# rpi_pwrspl.net
KiCad netlist of a schematic drawn in EAGLE
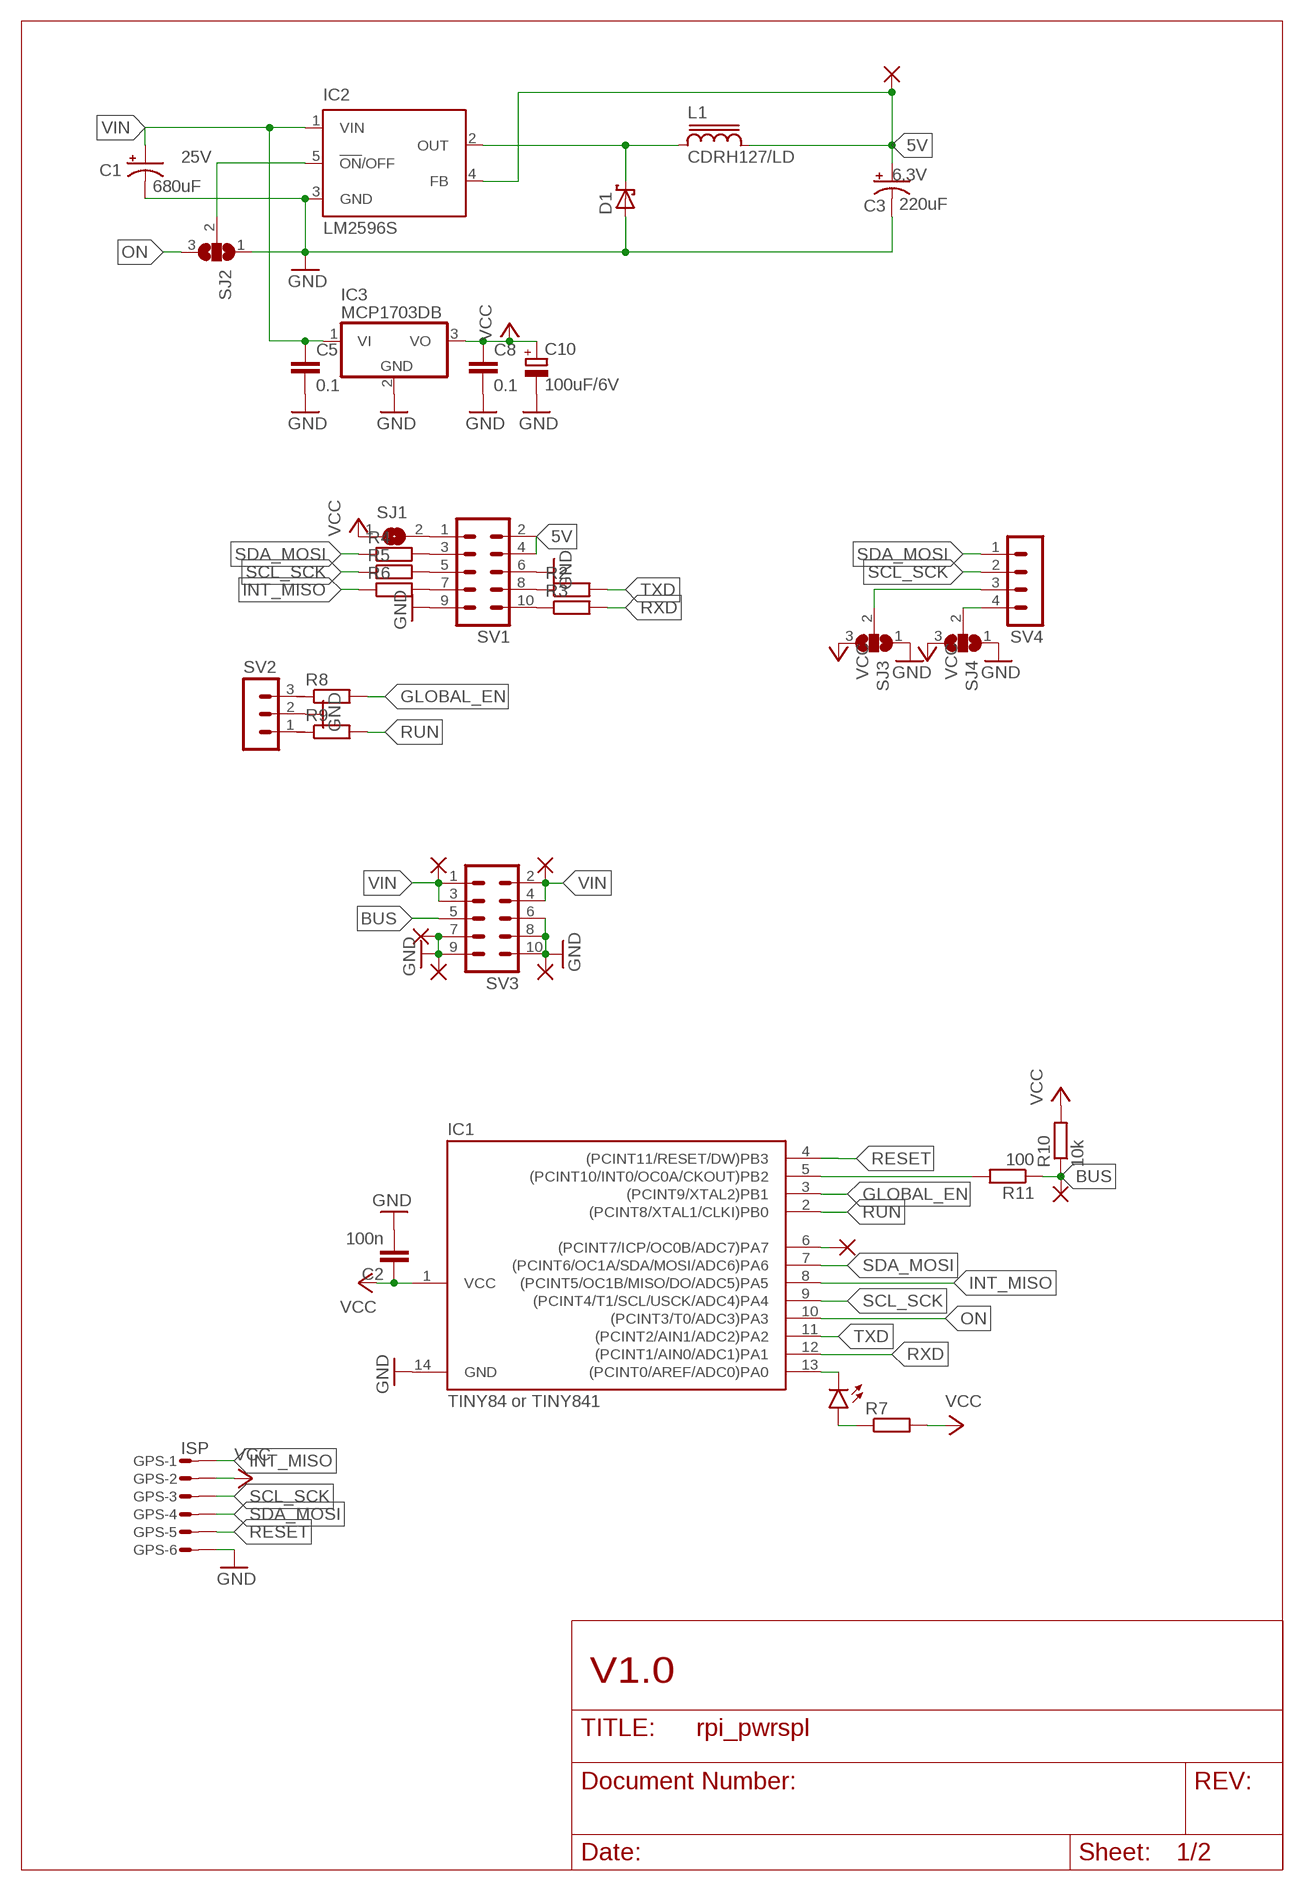
[diagram p0: schematic, sheet 1]

(export (version "E")
  (design (tool "Eeschema 10.0.6"))
  (components
    (comp (ref "C1")
      (value "680uF")
      (footprint "eagle-import:E5-10,5")
      (fields (field (name "VOLTAGE") "25V"))
      (libsource (lib "eagle-import") (part "CPOL-USE5-10.5"))
    )
    (comp (ref "C2")
      (value "100n")
      (footprint "eagle-import:C0805")
      (libsource (lib "eagle-import") (part "C-EUC0805"))
    )
    (comp (ref "C3")
      (value "220uF")
      (footprint "eagle-import:UD-6,3X5,8_NICHICON")
      (fields (field (name "VOLTAGE") "6.3V"))
      (libsource (lib "eagle-import") (part "CPOL-USUD-6,3X5,8"))
    )
    (comp (ref "C5")
      (value "0.1")
      (footprint "eagle-import:C0805")
      (libsource (lib "eagle-import") (part "C-EUC0805"))
    )
    (comp (ref "C8")
      (value "0.1")
      (footprint "eagle-import:C0805")
      (libsource (lib "eagle-import") (part "C-EUC0805"))
    )
    (comp (ref "C10")
      (value "100uF/6V")
      (footprint "eagle-import:B_3528-21R")
      (libsource (lib "eagle-import") (part "CPOL-EUB/3528-21R"))
    )
    (comp (ref "D1")
      (value "SCHOTTKY-DIODESMD")
      (footprint "eagle-import:SMB")
      (libsource (lib "eagle-import") (part "SCHOTTKY-DIODESMD"))
    )
    (comp (ref "GPS")
      (value "ISP")
      (footprint "eagle-import:MICROMATCH-6SMD")
      (libsource (lib "eagle-import") (part "MICROMATCH-6SMD"))
    )
    (comp (ref "IC1")
      (value "TINY84 or TINY841")
      (footprint "eagle-import:SOIC14")
      (libsource (lib "eagle-import") (part "TINY24/44/84-SSU"))
    )
    (comp (ref "IC2")
      (value "LM2596S")
      (footprint "eagle-import:TO263-5")
      (fields (field (name "MF") "NATIONAL SEMICONDUCTOR") (field (name "MPN") "LM2596S-ADJ/NOPB"))
      (libsource (lib "eagle-import") (part "LM2596S"))
    )
    (comp (ref "IC3")
      (value "MCP1703DB")
      (footprint "eagle-import:SOT223")
      (libsource (lib "eagle-import") (part "MCP1703DB"))
    )
    (comp (ref "L1")
      (value "CDRH127/LD")
      (footprint "eagle-import:CDRH127_LD")
      (libsource (lib "eagle-import") (part "CDRH127/LD"))
    )
    (comp (ref "LED")
      (value "LEDCHIPLED_0805")
      (footprint "eagle-import:CHIPLED_0805")
      (libsource (lib "eagle-import") (part "LEDCHIPLED_0805"))
    )
    (comp (ref "PAD1")
      (value "1,6/0,9")
      (footprint "eagle-import:1,6_0,9")
      (libsource (lib "eagle-import") (part "1,6/0,9"))
    )
    (comp (ref "PAD2")
      (value "1,6/0,9")
      (footprint "eagle-import:1,6_0,9")
      (libsource (lib "eagle-import") (part "1,6/0,9"))
    )
    (comp (ref "PAD3")
      (value "1,6/0,9")
      (footprint "eagle-import:1,6_0,9")
      (libsource (lib "eagle-import") (part "1,6/0,9"))
    )
    (comp (ref "PAD4")
      (value "2,54/1,1")
      (footprint "eagle-import:2,54_1,1")
      (libsource (lib "eagle-import") (part "2,54/1,1"))
    )
    (comp (ref "PAD5")
      (value "2,54/1,1")
      (footprint "eagle-import:2,54_1,1")
      (libsource (lib "eagle-import") (part "2,54/1,1"))
    )
    (comp (ref "PAD6")
      (value "1,6/0,9")
      (footprint "eagle-import:1,6_0,9")
      (libsource (lib "eagle-import") (part "1,6/0,9"))
    )
    (comp (ref "PAD7")
      (value "1,6/0,9")
      (footprint "eagle-import:1,6_0,9")
      (libsource (lib "eagle-import") (part "1,6/0,9"))
    )
    (comp (ref "PAD8")
      (value "2,54/1,1")
      (footprint "eagle-import:2,54_1,1")
      (libsource (lib "eagle-import") (part "2,54/1,1"))
    )
    (comp (ref "R2")
      (value "R-EU_M0805")
      (footprint "eagle-import:M0805")
      (libsource (lib "eagle-import") (part "R-EU_M0805"))
    )
    (comp (ref "R3")
      (value "R-EU_M0805")
      (footprint "eagle-import:M0805")
      (libsource (lib "eagle-import") (part "R-EU_M0805"))
    )
    (comp (ref "R4")
      (value "R-EU_M0805")
      (footprint "eagle-import:M0805")
      (libsource (lib "eagle-import") (part "R-EU_M0805"))
    )
    (comp (ref "R5")
      (value "R-EU_M0805")
      (footprint "eagle-import:M0805")
      (libsource (lib "eagle-import") (part "R-EU_M0805"))
    )
    (comp (ref "R6")
      (value "R-EU_M0805")
      (footprint "eagle-import:M0805")
      (libsource (lib "eagle-import") (part "R-EU_M0805"))
    )
    (comp (ref "R7")
      (value "100")
      (footprint "eagle-import:R0603")
      (libsource (lib "eagle-import") (part "R-EU_R0603"))
    )
    (comp (ref "R8")
      (value "R-EU_M0805")
      (footprint "eagle-import:M0805")
      (libsource (lib "eagle-import") (part "R-EU_M0805"))
    )
    (comp (ref "R9")
      (value "R-EU_M0805")
      (footprint "eagle-import:M0805")
      (libsource (lib "eagle-import") (part "R-EU_M0805"))
    )
    (comp (ref "R10")
      (value "10k")
      (footprint "eagle-import:M0805")
      (libsource (lib "eagle-import") (part "R-EU_M0805"))
    )
    (comp (ref "R11")
      (value "100")
      (footprint "eagle-import:M0805")
      (libsource (lib "eagle-import") (part "R-EU_M0805"))
    )
    (comp (ref "SJ1") (value "SJ") (footprint "eagle-import:SJ") (libsource (lib "eagle-import") (part "SJ")))
    (comp (ref "SJ2")
      (value "SJ2W")
      (footprint "eagle-import:SJ_2")
      (libsource (lib "eagle-import") (part "SJ2W"))
    )
    (comp (ref "SJ3")
      (value "SJ2W")
      (footprint "eagle-import:SJ_2")
      (libsource (lib "eagle-import") (part "SJ2W"))
    )
    (comp (ref "SJ4")
      (value "SJ2W")
      (footprint "eagle-import:SJ_2")
      (libsource (lib "eagle-import") (part "SJ2W"))
    )
    (comp (ref "SV1")
      (value "MA05-2")
      (footprint "eagle-import:MA05-2")
      (libsource (lib "eagle-import") (part "MA05-2"))
    )
    (comp (ref "SV2")
      (value "MA03-1")
      (footprint "eagle-import:MA03-1")
      (libsource (lib "eagle-import") (part "MA03-1"))
    )
    (comp (ref "SV3")
      (value "MA05-2")
      (footprint "eagle-import:MA05-2")
      (libsource (lib "eagle-import") (part "MA05-2"))
    )
    (comp (ref "SV4")
      (value "MA04-1")
      (footprint "eagle-import:MA04-1")
      (libsource (lib "eagle-import") (part "MA04-1"))
    )
  )
  (nets
    (net (code "1") (name "5V") (class "Default")
      (node (ref "C3") (pin "+") (pinfunction "+_+") (pintype "passive"))
      (node (ref "IC2") (pin "4") (pinfunction "FB_4") (pintype "input"))
      (node (ref "L1") (pin "2") (pinfunction "2_2") (pintype "passive"))
      (node (ref "PAD6") (pin "1") (pinfunction "P_1") (pintype "passive"))
      (node (ref "SV1") (pin "2") (pinfunction "2_2") (pintype "passive"))
      (node (ref "SV1") (pin "4") (pinfunction "4_4") (pintype "passive"))
    )
    (net (code "2") (name "BUS") (class "Default")
      (node (ref "PAD5") (pin "1") (pinfunction "P_1") (pintype "passive"))
      (node (ref "R10") (pin "1") (pinfunction "1_1") (pintype "passive"))
      (node (ref "R11") (pin "1") (pinfunction "1_1") (pintype "passive"))
      (node (ref "SV3") (pin "5") (pinfunction "5_5") (pintype "passive"))
    )
    (net (code "3") (name "GLOBAL_EN") (class "Default")
      (node (ref "IC1") (pin "3") (pinfunction "(PCINT9/XTAL2)PB1_3") (pintype "bidirectional"))
      (node (ref "R8") (pin "2") (pinfunction "2_2") (pintype "passive"))
    )
    (net (code "4") (name "GND") (class "Default")
      (node (ref "C1") (pin "-") (pinfunction "-_-") (pintype "passive"))
      (node (ref "C10") (pin "-") (pinfunction "-_-") (pintype "passive"))
      (node (ref "C2") (pin "2") (pinfunction "2_2") (pintype "passive"))
      (node (ref "C3") (pin "-") (pinfunction "-_-") (pintype "passive"))
      (node (ref "C5") (pin "2") (pinfunction "2_2") (pintype "passive"))
      (node (ref "C8") (pin "2") (pinfunction "2_2") (pintype "passive"))
      (node (ref "D1") (pin "A") (pinfunction "A_A") (pintype "passive"))
      (node (ref "GPS") (pin "6") (pinfunction "S_6") (pintype "passive"))
      (node (ref "IC1") (pin "14") (pinfunction "GND_14") (pintype "power_in"))
      (node (ref "IC2") (pin "3") (pinfunction "GND_3") (pintype "power_in"))
      (node (ref "IC3") (pin "2") (pinfunction "GND_2") (pintype "passive"))
      (node (ref "PAD2") (pin "1") (pinfunction "P_1") (pintype "passive"))
      (node (ref "PAD3") (pin "1") (pinfunction "P_1") (pintype "passive"))
      (node (ref "PAD8") (pin "1") (pinfunction "P_1") (pintype "passive"))
      (node (ref "SJ2") (pin "1") (pinfunction "1_1") (pintype "passive"))
      (node (ref "SJ3") (pin "1") (pinfunction "1_1") (pintype "passive"))
      (node (ref "SJ4") (pin "1") (pinfunction "1_1") (pintype "passive"))
      (node (ref "SV1") (pin "6") (pinfunction "6_6") (pintype "passive"))
      (node (ref "SV1") (pin "9") (pinfunction "9_9") (pintype "passive"))
      (node (ref "SV2") (pin "2") (pinfunction "2_2") (pintype "passive"))
      (node (ref "SV3") (pin "10") (pinfunction "10_10") (pintype "passive"))
      (node (ref "SV3") (pin "6") (pinfunction "6_6") (pintype "passive"))
      (node (ref "SV3") (pin "7") (pinfunction "7_7") (pintype "passive"))
      (node (ref "SV3") (pin "8") (pinfunction "8_8") (pintype "passive"))
      (node (ref "SV3") (pin "9") (pinfunction "9_9") (pintype "passive"))
    )
    (net (code "5") (name "INT_MISO") (class "Default")
      (node (ref "GPS") (pin "1") (pinfunction "S_1") (pintype "passive"))
      (node (ref "IC1") (pin "8") (pinfunction "(PCINT5/OC1B/MISO/DO/ADC5)PA5_8") (pintype "bidirectional"))
      (node (ref "R6") (pin "1") (pinfunction "1_1") (pintype "passive"))
    )
    (net (code "6") (name "Net-(IC1-(PCINT0{slash}AREF{slash}ADC0)PA0)") (class "Default")
      (node (ref "IC1") (pin "13") (pinfunction "(PCINT0/AREF/ADC0)PA0_13") (pintype "bidirectional"))
      (node (ref "LED") (pin "C") (pinfunction "C_C") (pintype "passive"))
    )
    (net (code "7") (name "Net-(IC1-(PCINT7{slash}ICP{slash}OC0B{slash}ADC7)PA7)") (class "Default")
      (node (ref "IC1") (pin "6") (pinfunction "(PCINT7/ICP/OC0B/ADC7)PA7_6") (pintype "bidirectional"))
      (node (ref "PAD7") (pin "1") (pinfunction "P_1") (pintype "passive"))
    )
    (net (code "8") (name "Net-(IC1-(PCINT10{slash}INT0{slash}OC0A{slash}CKOUT)PB2)") (class "Default")
      (node (ref "IC1") (pin "5") (pinfunction "(PCINT10/INT0/OC0A/CKOUT)PB2_5") (pintype "bidirectional"))
      (node (ref "R11") (pin "2") (pinfunction "2_2") (pintype "passive"))
    )
    (net (code "9") (name "Net-(IC2-OUT)") (class "Default")
      (node (ref "D1") (pin "C") (pinfunction "C_C") (pintype "passive"))
      (node (ref "IC2") (pin "2") (pinfunction "OUT_2") (pintype "output"))
      (node (ref "L1") (pin "1") (pinfunction "1_1") (pintype "passive"))
    )
    (net (code "10") (name "Net-(IC2-~{ON}{slash}OFF)") (class "Default")
      (node (ref "IC2") (pin "5") (pinfunction "~{ON}/OFF_5") (pintype "input"))
      (node (ref "SJ2") (pin "2") (pinfunction "2_2") (pintype "passive"))
    )
    (net (code "11") (name "Net-(LED-PadA)") (class "Default")
      (node (ref "LED") (pin "A") (pinfunction "A_A") (pintype "passive"))
      (node (ref "R7") (pin "1") (pinfunction "1_1") (pintype "passive"))
    )
    (net (code "12") (name "Net-(R2-Pad1)") (class "Default")
      (node (ref "R2") (pin "1") (pinfunction "1_1") (pintype "passive"))
      (node (ref "SV1") (pin "8") (pinfunction "8_8") (pintype "passive"))
    )
    (net (code "13") (name "Net-(R3-Pad1)") (class "Default")
      (node (ref "R3") (pin "1") (pinfunction "1_1") (pintype "passive"))
      (node (ref "SV1") (pin "10") (pinfunction "10_10") (pintype "passive"))
    )
    (net (code "14") (name "Net-(R4-Pad2)") (class "Default")
      (node (ref "R4") (pin "2") (pinfunction "2_2") (pintype "passive"))
      (node (ref "SV1") (pin "3") (pinfunction "3_3") (pintype "passive"))
    )
    (net (code "15") (name "Net-(R5-Pad2)") (class "Default")
      (node (ref "R5") (pin "2") (pinfunction "2_2") (pintype "passive"))
      (node (ref "SV1") (pin "5") (pinfunction "5_5") (pintype "passive"))
    )
    (net (code "16") (name "Net-(R6-Pad2)") (class "Default")
      (node (ref "R6") (pin "2") (pinfunction "2_2") (pintype "passive"))
      (node (ref "SV1") (pin "7") (pinfunction "7_7") (pintype "passive"))
    )
    (net (code "17") (name "Net-(SJ1-Pad2)") (class "Default")
      (node (ref "SJ1") (pin "2") (pinfunction "2_2") (pintype "passive"))
      (node (ref "SV1") (pin "1") (pinfunction "1_1") (pintype "passive"))
    )
    (net (code "18") (name "Net-(SJ3-Pad2)") (class "Default")
      (node (ref "SJ3") (pin "2") (pinfunction "2_2") (pintype "passive"))
      (node (ref "SV4") (pin "3") (pinfunction "3_3") (pintype "passive"))
    )
    (net (code "19") (name "Net-(SJ4-Pad2)") (class "Default")
      (node (ref "SJ4") (pin "2") (pinfunction "2_2") (pintype "passive"))
      (node (ref "SV4") (pin "4") (pinfunction "4_4") (pintype "passive"))
    )
    (net (code "20") (name "ON") (class "Default")
      (node (ref "IC1") (pin "10") (pinfunction "(PCINT3/T0/ADC3)PA3_10") (pintype "bidirectional"))
      (node (ref "SJ2") (pin "3") (pinfunction "3_3") (pintype "passive"))
    )
    (net (code "21") (name "RESET") (class "Default")
      (node (ref "GPS") (pin "5") (pinfunction "S_5") (pintype "passive"))
      (node (ref "IC1") (pin "4") (pinfunction "(PCINT11/RESET/DW)PB3_4") (pintype "bidirectional"))
    )
    (net (code "22") (name "RUN") (class "Default")
      (node (ref "IC1") (pin "2") (pinfunction "(PCINT8/XTAL1/CLKI)PB0_2") (pintype "bidirectional"))
      (node (ref "R9") (pin "2") (pinfunction "2_2") (pintype "passive"))
    )
    (net (code "23") (name "RXD") (class "Default")
      (node (ref "IC1") (pin "12") (pinfunction "(PCINT1/AIN0/ADC1)PA1_12") (pintype "bidirectional"))
      (node (ref "R3") (pin "2") (pinfunction "2_2") (pintype "passive"))
    )
    (net (code "24") (name "SCL_SCK") (class "Default")
      (node (ref "GPS") (pin "3") (pinfunction "S_3") (pintype "passive"))
      (node (ref "IC1") (pin "9") (pinfunction "(PCINT4/T1/SCL/USCK/ADC4)PA4_9") (pintype "bidirectional"))
      (node (ref "R5") (pin "1") (pinfunction "1_1") (pintype "passive"))
      (node (ref "SV4") (pin "2") (pinfunction "2_2") (pintype "passive"))
    )
    (net (code "25") (name "SDA_MOSI") (class "Default")
      (node (ref "GPS") (pin "4") (pinfunction "S_4") (pintype "passive"))
      (node (ref "IC1") (pin "7") (pinfunction "(PCINT6/OC1A/SDA/MOSI/ADC6)PA6_7") (pintype "bidirectional"))
      (node (ref "R4") (pin "1") (pinfunction "1_1") (pintype "passive"))
      (node (ref "SV4") (pin "1") (pinfunction "1_1") (pintype "passive"))
    )
    (net (code "26") (name "TXD") (class "Default")
      (node (ref "IC1") (pin "11") (pinfunction "(PCINT2/AIN1/ADC2)PA2_11") (pintype "bidirectional"))
      (node (ref "R2") (pin "2") (pinfunction "2_2") (pintype "passive"))
    )
    (net (code "27") (name "VCC") (class "Default")
      (node (ref "C10") (pin "+") (pinfunction "+_+") (pintype "passive"))
      (node (ref "C2") (pin "1") (pinfunction "1_1") (pintype "passive"))
      (node (ref "C8") (pin "1") (pinfunction "1_1") (pintype "passive"))
      (node (ref "GPS") (pin "2") (pinfunction "S_2") (pintype "passive"))
      (node (ref "IC1") (pin "1") (pinfunction "VCC_1") (pintype "power_in"))
      (node (ref "IC3") (pin "3") (pinfunction "VO_3") (pintype "passive"))
      (node (ref "R10") (pin "2") (pinfunction "2_2") (pintype "passive"))
      (node (ref "R7") (pin "2") (pinfunction "2_2") (pintype "passive"))
      (node (ref "SJ1") (pin "1") (pinfunction "1_1") (pintype "passive"))
      (node (ref "SJ3") (pin "3") (pinfunction "3_3") (pintype "passive"))
      (node (ref "SJ4") (pin "3") (pinfunction "3_3") (pintype "passive"))
    )
    (net (code "28") (name "VIN") (class "Default")
      (node (ref "C1") (pin "+") (pinfunction "+_+") (pintype "passive"))
      (node (ref "C5") (pin "1") (pinfunction "1_1") (pintype "passive"))
      (node (ref "IC2") (pin "1") (pinfunction "VIN_1") (pintype "input"))
      (node (ref "IC3") (pin "1") (pinfunction "VI_1") (pintype "input"))
      (node (ref "PAD1") (pin "1") (pinfunction "P_1") (pintype "passive"))
      (node (ref "PAD4") (pin "1") (pinfunction "P_1") (pintype "passive"))
      (node (ref "SV3") (pin "1") (pinfunction "1_1") (pintype "passive"))
      (node (ref "SV3") (pin "2") (pinfunction "2_2") (pintype "passive"))
      (node (ref "SV3") (pin "3") (pinfunction "3_3") (pintype "passive"))
      (node (ref "SV3") (pin "4") (pinfunction "4_4") (pintype "passive"))
    )
    (net (code "29") (name "unconnected-(R8-Pad1)") (class "Default")
      (node (ref "R8") (pin "1") (pinfunction "1_1") (pintype "passive"))
    )
    (net (code "30") (name "unconnected-(R9-Pad1)") (class "Default")
      (node (ref "R9") (pin "1") (pinfunction "1_1") (pintype "passive"))
    )
    (net (code "31") (name "unconnected-(SV2-Pad1)") (class "Default")
      (node (ref "SV2") (pin "1") (pinfunction "1_1") (pintype "passive"))
    )
    (net (code "32") (name "unconnected-(SV2-Pad3)") (class "Default")
      (node (ref "SV2") (pin "3") (pinfunction "3_3") (pintype "passive"))
    )
  )
)
